# UART_Splitter.net
KiCad netlist of a schematic drawn in EAGLE
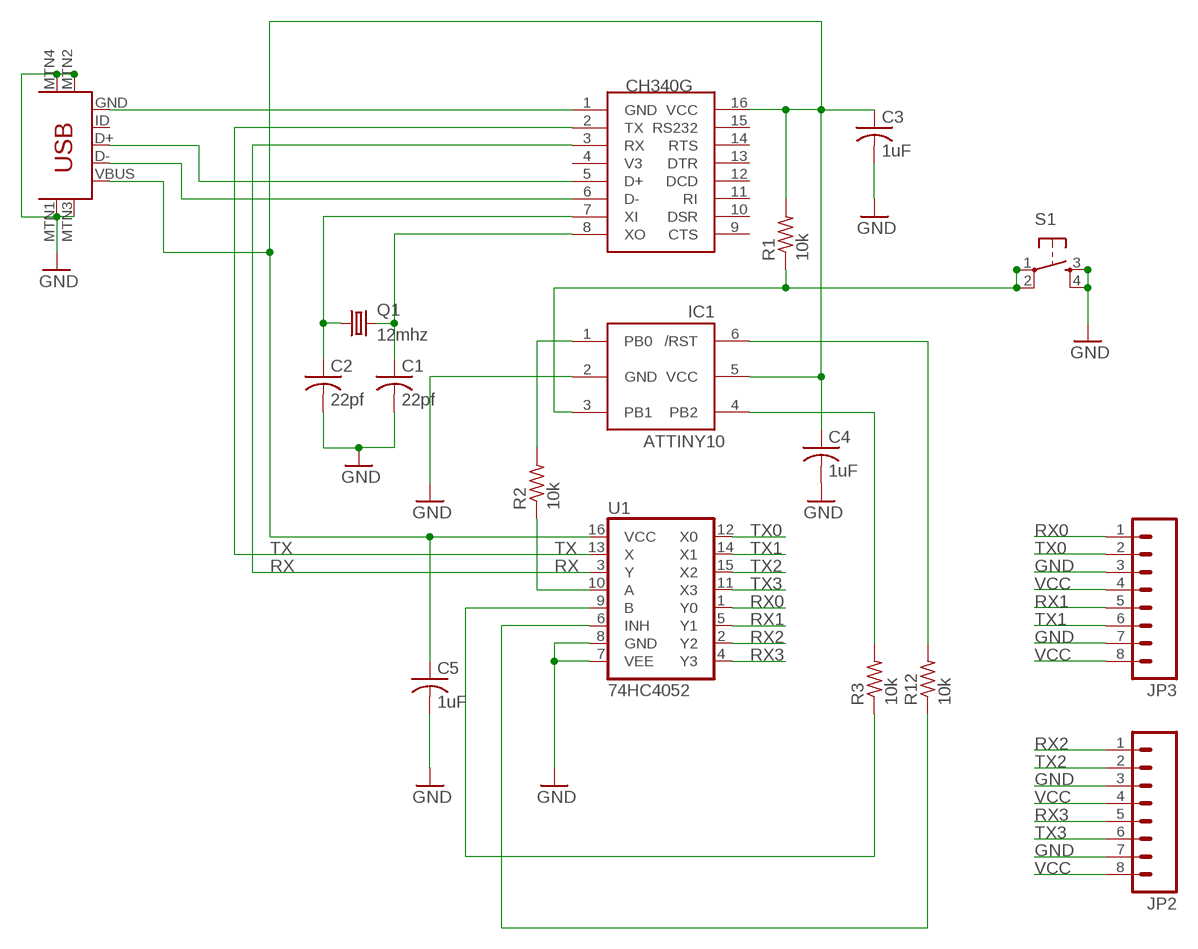
[diagram p0: schematic, sheet 1]
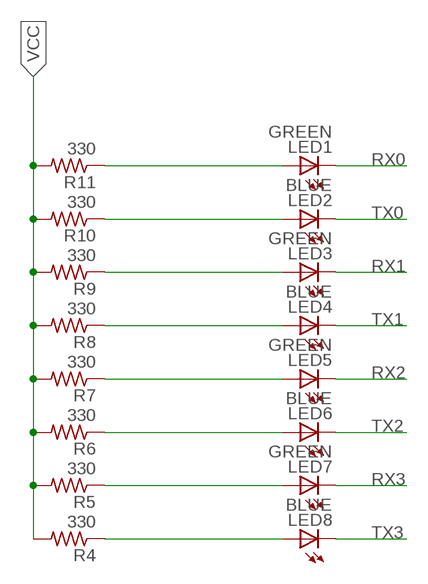
[diagram p1: schematic, sheet 2]

(export (version "E")
  (design (tool "Eeschema 10.0.6"))
  (components
    (comp (ref "C1")
      (value "22pf")
      (footprint "eagle-import:C0402K")
      (libsource (lib "eagle-import") (part "C-USC0402K"))
    )
    (comp (ref "C2")
      (value "22pf")
      (footprint "eagle-import:C0402K")
      (libsource (lib "eagle-import") (part "C-USC0402K"))
    )
    (comp (ref "C3")
      (value "1uF")
      (footprint "eagle-import:C0402K")
      (libsource (lib "eagle-import") (part "C-USC0402K"))
    )
    (comp (ref "C4")
      (value "1uF")
      (footprint "eagle-import:C0402K")
      (libsource (lib "eagle-import") (part "C-USC0402K"))
    )
    (comp (ref "C5")
      (value "1uF")
      (footprint "eagle-import:C0402K")
      (libsource (lib "eagle-import") (part "C-USC0402K"))
    )
    (comp (ref "IC1")
      (value "ATTINY10")
      (footprint "eagle-import:SOT23-6")
      (libsource (lib "eagle-import") (part "ATTINY10"))
    )
    (comp (ref "JP2")
      (value "M081X08")
      (footprint "eagle-import:1X08")
      (libsource (lib "eagle-import") (part "M081X08"))
    )
    (comp (ref "JP3")
      (value "M081X08")
      (footprint "eagle-import:1X08")
      (libsource (lib "eagle-import") (part "M081X08"))
    )
    (comp (ref "Q1")
      (value "12mhz")
      (footprint "eagle-import:HC49UP")
      (libsource (lib "eagle-import") (part "CRYSTALHC49UP"))
    )
    (comp (ref "R1")
      (value "10k")
      (footprint "eagle-import:R0402")
      (libsource (lib "eagle-import") (part "R-US_R0402"))
    )
    (comp (ref "R2")
      (value "10k")
      (footprint "eagle-import:R0402")
      (libsource (lib "eagle-import") (part "R-US_R0402"))
    )
    (comp (ref "R3")
      (value "10k")
      (footprint "eagle-import:R0402")
      (libsource (lib "eagle-import") (part "R-US_R0402"))
    )
    (comp (ref "R12")
      (value "10k")
      (footprint "eagle-import:R0402")
      (libsource (lib "eagle-import") (part "R-US_R0402"))
    )
    (comp (ref "S1")
      (value "TAC_SWITCHSMD")
      (footprint "eagle-import:TACTILE_SWITCH_SMD")
      (libsource (lib "eagle-import") (part "TAC_SWITCHSMD"))
    )
    (comp (ref "U$1")
      (value "CH340G")
      (footprint "eagle-import:SOIC16")
      (libsource (lib "eagle-import") (part "CH340G"))
    )
    (comp (ref "U$2")
      (value "USB-MINIB-5PIN")
      (footprint "eagle-import:USB-MINIB")
      (libsource (lib "eagle-import") (part "USB-MINIB-5PIN"))
    )
    (comp (ref "U1")
      (value "74HC4052")
      (footprint "eagle-import:SO16")
      (libsource (lib "eagle-import") (part "74HC4052SO"))
    )
    (comp (ref "LED1")
      (value "GREEN")
      (footprint "eagle-import:SML0603")
      (libsource (lib "eagle-import") (part "LEDSML0603"))
    )
    (comp (ref "LED2")
      (value "BLUE")
      (footprint "eagle-import:SML0603")
      (libsource (lib "eagle-import") (part "LEDSML0603"))
    )
    (comp (ref "LED3")
      (value "GREEN")
      (footprint "eagle-import:SML0603")
      (libsource (lib "eagle-import") (part "LEDSML0603"))
    )
    (comp (ref "LED4")
      (value "BLUE")
      (footprint "eagle-import:SML0603")
      (libsource (lib "eagle-import") (part "LEDSML0603"))
    )
    (comp (ref "LED5")
      (value "GREEN")
      (footprint "eagle-import:SML0603")
      (libsource (lib "eagle-import") (part "LEDSML0603"))
    )
    (comp (ref "LED6")
      (value "BLUE")
      (footprint "eagle-import:SML0603")
      (libsource (lib "eagle-import") (part "LEDSML0603"))
    )
    (comp (ref "LED7")
      (value "GREEN")
      (footprint "eagle-import:SML0603")
      (libsource (lib "eagle-import") (part "LEDSML0603"))
    )
    (comp (ref "LED8")
      (value "BLUE")
      (footprint "eagle-import:SML0603")
      (libsource (lib "eagle-import") (part "LEDSML0603"))
    )
    (comp (ref "R4")
      (value "330")
      (footprint "eagle-import:R0402")
      (libsource (lib "eagle-import") (part "R-US_R0402"))
    )
    (comp (ref "R5")
      (value "330")
      (footprint "eagle-import:R0402")
      (libsource (lib "eagle-import") (part "R-US_R0402"))
    )
    (comp (ref "R6")
      (value "330")
      (footprint "eagle-import:R0402")
      (libsource (lib "eagle-import") (part "R-US_R0402"))
    )
    (comp (ref "R7")
      (value "330")
      (footprint "eagle-import:R0402")
      (libsource (lib "eagle-import") (part "R-US_R0402"))
    )
    (comp (ref "R8")
      (value "330")
      (footprint "eagle-import:R0402")
      (libsource (lib "eagle-import") (part "R-US_R0402"))
    )
    (comp (ref "R9")
      (value "330")
      (footprint "eagle-import:R0402")
      (libsource (lib "eagle-import") (part "R-US_R0402"))
    )
    (comp (ref "R10")
      (value "330")
      (footprint "eagle-import:R0402")
      (libsource (lib "eagle-import") (part "R-US_R0402"))
    )
    (comp (ref "R11")
      (value "330")
      (footprint "eagle-import:R0402")
      (libsource (lib "eagle-import") (part "R-US_R0402"))
    )
  )
  (nets
    (net (code "1") (name "GND") (class "Default")
      (node (ref "C1") (pin "2") (pinfunction "2_2") (pintype "passive"))
      (node (ref "C2") (pin "2") (pinfunction "2_2") (pintype "passive"))
      (node (ref "C3") (pin "2") (pinfunction "2_2") (pintype "passive"))
      (node (ref "C4") (pin "2") (pinfunction "2_2") (pintype "passive"))
      (node (ref "C5") (pin "2") (pinfunction "2_2") (pintype "passive"))
      (node (ref "IC1") (pin "2") (pinfunction "GND_2") (pintype "power_in"))
      (node (ref "JP2") (pin "3") (pinfunction "3_3") (pintype "passive"))
      (node (ref "JP2") (pin "7") (pinfunction "7_7") (pintype "passive"))
      (node (ref "JP3") (pin "3") (pinfunction "3_3") (pintype "passive"))
      (node (ref "JP3") (pin "7") (pinfunction "7_7") (pintype "passive"))
      (node (ref "S1") (pin "3") (pinfunction "3_3") (pintype "passive"))
      (node (ref "S1") (pin "4") (pinfunction "4_4") (pintype "passive"))
      (node (ref "U$1") (pin "1") (pinfunction "GND_1") (pintype "bidirectional"))
      (node (ref "U$2") (pin "GND") (pinfunction "GND_GND") (pintype "bidirectional"))
      (node (ref "U$2") (pin "MTN1") (pinfunction "MTN2_MTN1") (pintype "bidirectional"))
      (node (ref "U$2") (pin "MTN2") (pinfunction "MTN3_MTN2") (pintype "bidirectional"))
      (node (ref "U$2") (pin "MTN3") (pinfunction "MTN1_MTN3") (pintype "bidirectional"))
      (node (ref "U$2") (pin "MTN4") (pinfunction "MTN4_MTN4") (pintype "bidirectional"))
      (node (ref "U1") (pin "7") (pinfunction "VEE_7") (pintype "power_in"))
      (node (ref "U1") (pin "8") (pinfunction "GND_8") (pintype "power_in"))
    )
    (net (code "2") (name "Net-(IC1-PB0)") (class "Default")
      (node (ref "IC1") (pin "1") (pinfunction "PB0_1") (pintype "bidirectional"))
      (node (ref "R2") (pin "2") (pinfunction "2_2") (pintype "passive"))
    )
    (net (code "3") (name "Net-(IC1-PB1)") (class "Default")
      (node (ref "IC1") (pin "3") (pinfunction "PB1_3") (pintype "bidirectional"))
      (node (ref "R1") (pin "1") (pinfunction "1_1") (pintype "passive"))
      (node (ref "S1") (pin "1") (pinfunction "1_1") (pintype "passive"))
      (node (ref "S1") (pin "2") (pinfunction "2_2") (pintype "passive"))
    )
    (net (code "4") (name "Net-(IC1-PB2)") (class "Default")
      (node (ref "IC1") (pin "4") (pinfunction "PB2_4") (pintype "bidirectional"))
      (node (ref "R3") (pin "2") (pinfunction "2_2") (pintype "passive"))
    )
    (net (code "5") (name "Net-(IC1-{slash}RST)") (class "Default")
      (node (ref "IC1") (pin "6") (pinfunction "/RST_6") (pintype "bidirectional"))
      (node (ref "R12") (pin "2") (pinfunction "2_2") (pintype "passive"))
    )
    (net (code "6") (name "Net-(LED1-PadA)") (class "Default")
      (node (ref "LED1") (pin "A") (pinfunction "A_A") (pintype "passive"))
      (node (ref "R11") (pin "1") (pinfunction "1_1") (pintype "passive"))
    )
    (net (code "7") (name "Net-(LED2-PadA)") (class "Default")
      (node (ref "LED2") (pin "A") (pinfunction "A_A") (pintype "passive"))
      (node (ref "R10") (pin "1") (pinfunction "1_1") (pintype "passive"))
    )
    (net (code "8") (name "Net-(LED3-PadA)") (class "Default")
      (node (ref "LED3") (pin "A") (pinfunction "A_A") (pintype "passive"))
      (node (ref "R9") (pin "1") (pinfunction "1_1") (pintype "passive"))
    )
    (net (code "9") (name "Net-(LED4-PadA)") (class "Default")
      (node (ref "LED4") (pin "A") (pinfunction "A_A") (pintype "passive"))
      (node (ref "R8") (pin "1") (pinfunction "1_1") (pintype "passive"))
    )
    (net (code "10") (name "Net-(LED5-PadA)") (class "Default")
      (node (ref "LED5") (pin "A") (pinfunction "A_A") (pintype "passive"))
      (node (ref "R7") (pin "1") (pinfunction "1_1") (pintype "passive"))
    )
    (net (code "11") (name "Net-(LED6-PadA)") (class "Default")
      (node (ref "LED6") (pin "A") (pinfunction "A_A") (pintype "passive"))
      (node (ref "R6") (pin "1") (pinfunction "1_1") (pintype "passive"))
    )
    (net (code "12") (name "Net-(LED7-PadA)") (class "Default")
      (node (ref "LED7") (pin "A") (pinfunction "A_A") (pintype "passive"))
      (node (ref "R5") (pin "1") (pinfunction "1_1") (pintype "passive"))
    )
    (net (code "13") (name "Net-(LED8-PadA)") (class "Default")
      (node (ref "LED8") (pin "A") (pinfunction "A_A") (pintype "passive"))
      (node (ref "R4") (pin "1") (pinfunction "1_1") (pintype "passive"))
    )
    (net (code "14") (name "Net-(U$1-D+)") (class "Default")
      (node (ref "U$1") (pin "5") (pinfunction "D+_5") (pintype "bidirectional"))
      (node (ref "U$2") (pin "D+") (pinfunction "D+_D+") (pintype "bidirectional"))
    )
    (net (code "15") (name "Net-(U$1-D-)") (class "Default")
      (node (ref "U$1") (pin "6") (pinfunction "D-_6") (pintype "bidirectional"))
      (node (ref "U$2") (pin "D-") (pinfunction "D-_D-") (pintype "bidirectional"))
    )
    (net (code "16") (name "Net-(U$1-XI)") (class "Default")
      (node (ref "C2") (pin "1") (pinfunction "1_1") (pintype "passive"))
      (node (ref "Q1") (pin "1") (pinfunction "1_1") (pintype "passive"))
      (node (ref "U$1") (pin "7") (pinfunction "XI_7") (pintype "bidirectional"))
    )
    (net (code "17") (name "Net-(U$1-XO)") (class "Default")
      (node (ref "C1") (pin "1") (pinfunction "1_1") (pintype "passive"))
      (node (ref "Q1") (pin "2") (pinfunction "2_2") (pintype "passive"))
      (node (ref "U$1") (pin "8") (pinfunction "XO_8") (pintype "bidirectional"))
    )
    (net (code "18") (name "Net-(U1-A)") (class "Default")
      (node (ref "R2") (pin "1") (pinfunction "1_1") (pintype "passive"))
      (node (ref "U1") (pin "10") (pinfunction "A_10") (pintype "input"))
    )
    (net (code "19") (name "Net-(U1-B)") (class "Default")
      (node (ref "R3") (pin "1") (pinfunction "1_1") (pintype "passive"))
      (node (ref "U1") (pin "9") (pinfunction "B_9") (pintype "input"))
    )
    (net (code "20") (name "Net-(U1-INH)") (class "Default")
      (node (ref "R12") (pin "1") (pinfunction "1_1") (pintype "passive"))
      (node (ref "U1") (pin "6") (pinfunction "INH_6") (pintype "input"))
    )
    (net (code "21") (name "RX") (class "Default")
      (node (ref "U$1") (pin "3") (pinfunction "RX_3") (pintype "bidirectional"))
      (node (ref "U1") (pin "3") (pinfunction "Y_3") (pintype "bidirectional"))
    )
    (net (code "22") (name "RX0") (class "Default")
      (node (ref "JP3") (pin "1") (pinfunction "1_1") (pintype "passive"))
      (node (ref "LED1") (pin "C") (pinfunction "C_C") (pintype "passive"))
      (node (ref "U1") (pin "1") (pinfunction "Y0_1") (pintype "bidirectional"))
    )
    (net (code "23") (name "RX1") (class "Default")
      (node (ref "JP3") (pin "5") (pinfunction "5_5") (pintype "passive"))
      (node (ref "LED3") (pin "C") (pinfunction "C_C") (pintype "passive"))
      (node (ref "U1") (pin "5") (pinfunction "Y1_5") (pintype "bidirectional"))
    )
    (net (code "24") (name "RX2") (class "Default")
      (node (ref "JP2") (pin "1") (pinfunction "1_1") (pintype "passive"))
      (node (ref "LED5") (pin "C") (pinfunction "C_C") (pintype "passive"))
      (node (ref "U1") (pin "2") (pinfunction "Y2_2") (pintype "bidirectional"))
    )
    (net (code "25") (name "RX3") (class "Default")
      (node (ref "JP2") (pin "5") (pinfunction "5_5") (pintype "passive"))
      (node (ref "LED7") (pin "C") (pinfunction "C_C") (pintype "passive"))
      (node (ref "U1") (pin "4") (pinfunction "Y3_4") (pintype "bidirectional"))
    )
    (net (code "26") (name "TX") (class "Default")
      (node (ref "U$1") (pin "2") (pinfunction "TX_2") (pintype "bidirectional"))
      (node (ref "U1") (pin "13") (pinfunction "X_13") (pintype "bidirectional"))
    )
    (net (code "27") (name "TX0") (class "Default")
      (node (ref "JP3") (pin "2") (pinfunction "2_2") (pintype "passive"))
      (node (ref "LED2") (pin "C") (pinfunction "C_C") (pintype "passive"))
      (node (ref "U1") (pin "12") (pinfunction "X0_12") (pintype "bidirectional"))
    )
    (net (code "28") (name "TX1") (class "Default")
      (node (ref "JP3") (pin "6") (pinfunction "6_6") (pintype "passive"))
      (node (ref "LED4") (pin "C") (pinfunction "C_C") (pintype "passive"))
      (node (ref "U1") (pin "14") (pinfunction "X1_14") (pintype "bidirectional"))
    )
    (net (code "29") (name "TX2") (class "Default")
      (node (ref "JP2") (pin "2") (pinfunction "2_2") (pintype "passive"))
      (node (ref "LED6") (pin "C") (pinfunction "C_C") (pintype "passive"))
      (node (ref "U1") (pin "15") (pinfunction "X2_15") (pintype "bidirectional"))
    )
    (net (code "30") (name "TX3") (class "Default")
      (node (ref "JP2") (pin "6") (pinfunction "6_6") (pintype "passive"))
      (node (ref "LED8") (pin "C") (pinfunction "C_C") (pintype "passive"))
      (node (ref "U1") (pin "11") (pinfunction "X3_11") (pintype "bidirectional"))
    )
    (net (code "31") (name "VCC") (class "Default")
      (node (ref "C3") (pin "1") (pinfunction "1_1") (pintype "passive"))
      (node (ref "C4") (pin "1") (pinfunction "1_1") (pintype "passive"))
      (node (ref "C5") (pin "1") (pinfunction "1_1") (pintype "passive"))
      (node (ref "IC1") (pin "5") (pinfunction "VCC_5") (pintype "power_in"))
      (node (ref "JP2") (pin "4") (pinfunction "4_4") (pintype "passive"))
      (node (ref "JP2") (pin "8") (pinfunction "8_8") (pintype "passive"))
      (node (ref "JP3") (pin "4") (pinfunction "4_4") (pintype "passive"))
      (node (ref "JP3") (pin "8") (pinfunction "8_8") (pintype "passive"))
      (node (ref "R1") (pin "2") (pinfunction "2_2") (pintype "passive"))
      (node (ref "R10") (pin "2") (pinfunction "2_2") (pintype "passive"))
      (node (ref "R11") (pin "2") (pinfunction "2_2") (pintype "passive"))
      (node (ref "R4") (pin "2") (pinfunction "2_2") (pintype "passive"))
      (node (ref "R5") (pin "2") (pinfunction "2_2") (pintype "passive"))
      (node (ref "R6") (pin "2") (pinfunction "2_2") (pintype "passive"))
      (node (ref "R7") (pin "2") (pinfunction "2_2") (pintype "passive"))
      (node (ref "R8") (pin "2") (pinfunction "2_2") (pintype "passive"))
      (node (ref "R9") (pin "2") (pinfunction "2_2") (pintype "passive"))
      (node (ref "U$1") (pin "16") (pinfunction "VCC_16") (pintype "bidirectional"))
      (node (ref "U$2") (pin "VBUS") (pinfunction "VBUS_VBUS") (pintype "bidirectional"))
      (node (ref "U1") (pin "16") (pinfunction "VCC_16") (pintype "power_in"))
    )
    (net (code "32") (name "unconnected-(U$1-CTS-Pad9)") (class "Default")
      (node (ref "U$1") (pin "9") (pinfunction "CTS_9") (pintype "bidirectional"))
    )
    (net (code "33") (name "unconnected-(U$1-DCD-Pad12)") (class "Default")
      (node (ref "U$1") (pin "12") (pinfunction "DCD_12") (pintype "bidirectional"))
    )
    (net (code "34") (name "unconnected-(U$1-DSR-Pad10)") (class "Default")
      (node (ref "U$1") (pin "10") (pinfunction "DSR_10") (pintype "bidirectional"))
    )
    (net (code "35") (name "unconnected-(U$1-DTR-Pad13)") (class "Default")
      (node (ref "U$1") (pin "13") (pinfunction "DTR_13") (pintype "bidirectional"))
    )
    (net (code "36") (name "unconnected-(U$1-RI-Pad11)") (class "Default")
      (node (ref "U$1") (pin "11") (pinfunction "RI_11") (pintype "bidirectional"))
    )
    (net (code "37") (name "unconnected-(U$1-RS232-Pad15)") (class "Default")
      (node (ref "U$1") (pin "15") (pinfunction "RS232_15") (pintype "bidirectional"))
    )
    (net (code "38") (name "unconnected-(U$1-RTS-Pad14)") (class "Default")
      (node (ref "U$1") (pin "14") (pinfunction "RTS_14") (pintype "bidirectional"))
    )
    (net (code "39") (name "unconnected-(U$1-V3-Pad4)") (class "Default")
      (node (ref "U$1") (pin "4") (pinfunction "V3_4") (pintype "bidirectional"))
    )
    (net (code "40") (name "unconnected-(U$2-PadID)") (class "Default")
      (node (ref "U$2") (pin "ID") (pinfunction "ID_ID") (pintype "bidirectional"))
    )
  )
)
